# H21R4_Backend.net
KiCad netlist of a schematic drawn in Altium Designer
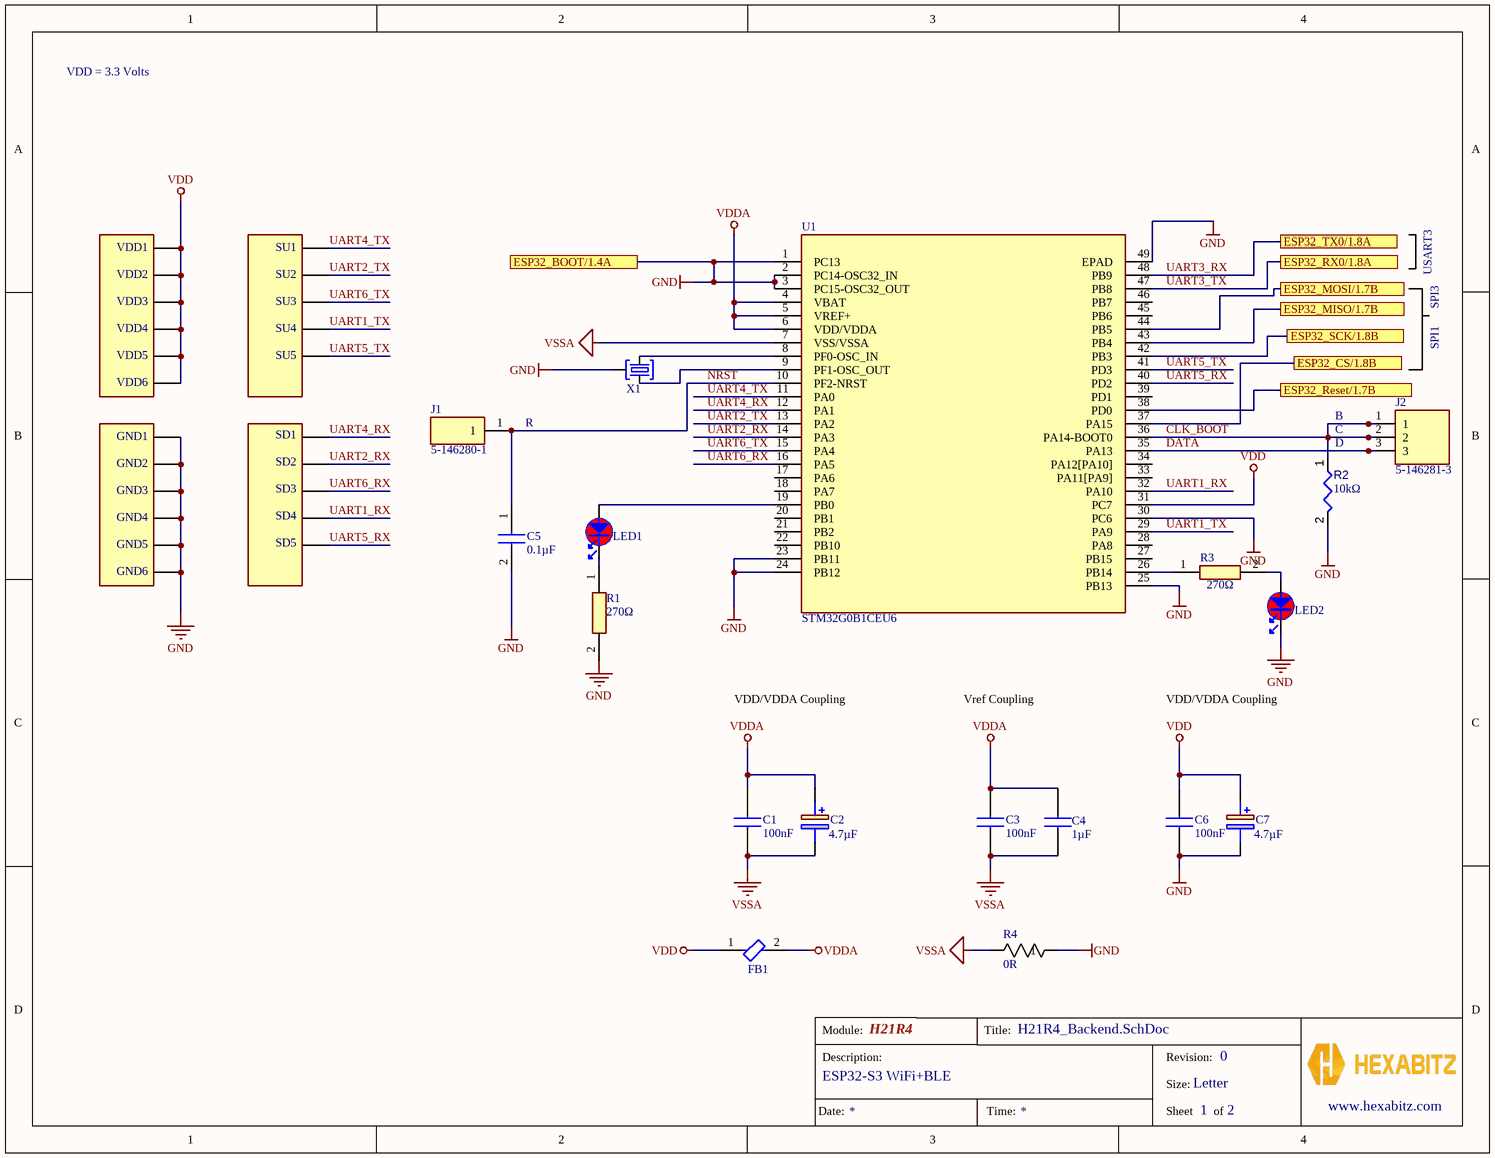
[diagram p0: H21R4_Backend.SchDoc]

(export (version "E")
  (design (tool "Eeschema 10.0.6"))
  (components
    (comp (ref "C1")
      (value "100nF")
      (footprint "CAPC1608X87N")
      (description "Multilayer Ceramic Capacitors MLCC - SMD/SMT .1UF     10V   10%        0603")
      (fields (field (name "MANUFACTURER_PART_NUMBER") "C0603C104K8RAC7867"))
      (libsource (lib "Wesley Walker") (part "C0603C104K8RAC7867"))
    )
    (comp (ref "C2")
      (value "4.7µF")
      (footprint "CAPPM2012X100N")
      (fields
        (field (name "MANUFACTURER_PART_NUMBER") "10TPU4R7MSI")
        (field (name "MOUSER PART NUMBER") "667-10TPU4R7MSI")
      )
      (libsource (lib "Wesley Walker") (part "10TPU4R7MSI"))
    )
    (comp (ref "C3")
      (value "100nF")
      (footprint "CAPC1608X87N")
      (description "Multilayer Ceramic Capacitors MLCC - SMD/SMT .1UF     10V   10%        0603")
      (fields (field (name "MANUFACTURER_PART_NUMBER") "C0603C104K8RAC7867"))
      (libsource (lib "Wesley Walker") (part "C0603C104K8RAC7867"))
    )
    (comp (ref "C4")
      (value "1µF")
      (footprint "CAPC2012X145N")
      (fields
        (field (name "ARROW PART NUMBER") "CC0805KKX7R7BB105")
        (field (name "MOUSER PART NUMBER") "603-CC805KKX7R7BB105")
      )
      (libsource (lib "Wesley Walker") (part "CC0805KKX7R7BB105"))
    )
    (comp (ref "C5")
      (value "0.1µF")
      (footprint "SamacSys:CAPC1608X87N")
      (description "Capacitor")
      (fields (field (name "MANUFACTURER_PART_NUMBER") "C0603C104K8RAC7867"))
      (libsource (lib "*") (part "C0603C104K8RAC7867"))
    )
    (comp (ref "C6")
      (value "100nF")
      (footprint "CAPC1608X87N")
      (description "Multilayer Ceramic Capacitors MLCC - SMD/SMT .1UF     10V   10%        0603")
      (fields (field (name "MANUFACTURER_PART_NUMBER") "C0603C104K8RAC7867"))
      (libsource (lib "Wesley Walker") (part "C0603C104K8RAC7867"))
    )
    (comp (ref "C7")
      (value "4.7µF")
      (footprint "CAPPM2012X100N")
      (fields
        (field (name "MANUFACTURER_PART_NUMBER") "10TPU4R7MSI")
        (field (name "MOUSER PART NUMBER") "667-10TPU4R7MSI")
      )
      (libsource (lib "Wesley Walker") (part "10TPU4R7MSI"))
    )
    (comp (ref "FB1")
      (value "MMZ1608Y300B")
      (footprint "FP-MMZ1608-0_8-MFG")
      (description "Ferrite Beads 0603 30ohms 1500mA Signal Line AEC-Q200")
      (fields
        (field (name "MANUFACTURER PART NUMBER") "MMZ1608Y300BTD25")
        (field (name "MANUFACTURER") "TDK")
      )
      (libsource (lib "Wesley Walker") (part "MMZ1608Y300B"))
    )
    (comp (ref "GND1")
      (value "HEXABIT_UART_PORT")
      (footprint "HEXABIT_POWER_PORT_D")
      (libsource (lib "hexabitz_connectors.Library") (part "HEXABIT_POWER_PORT_D"))
    )
    (comp (ref "GND2")
      (value "HEXABIT_UART_PORT")
      (footprint "HEXABIT_POWER_PORT_D")
      (libsource (lib "hexabitz_connectors.Library") (part "HEXABIT_POWER_PORT_D"))
    )
    (comp (ref "GND3")
      (value "HEXABIT_UART_PORT")
      (footprint "HEXABIT_POWER_PORT_D")
      (libsource (lib "hexabitz_connectors.Library") (part "HEXABIT_POWER_PORT_D"))
    )
    (comp (ref "GND4")
      (value "HEXABIT_UART_PORT")
      (footprint "HEXABIT_POWER_PORT_D")
      (libsource (lib "hexabitz_connectors.Library") (part "HEXABIT_POWER_PORT_D"))
    )
    (comp (ref "GND5")
      (value "HEXABIT_UART_PORT")
      (footprint "HEXABIT_POWER_PORT_D")
      (libsource (lib "hexabitz_connectors.Library") (part "HEXABIT_POWER_PORT_D"))
    )
    (comp (ref "GND6")
      (value "HEXABIT_UART_PORT")
      (footprint "HEXABIT_POWER_PORT_D")
      (libsource (lib "hexabitz_connectors.Library") (part "HEXABIT_POWER_PORT_D"))
    )
    (comp (ref "J1")
      (value "5-146280-1")
      (footprint "HDRV1W67P0X254_1X1_213X234X821P")
      (description "AMP - TE CONNECTIVITY - 5-146280-1 - 01 MODII HDR SRST B/A LF")
      (fields (field (name "MOUSER PART NUMBER") "571-51462801"))
      (libsource (lib "Wesley Walker") (part "5-146280-1"))
    )
    (comp (ref "J2")
      (value "5-146281-3")
      (footprint "SamacSys:HDRV3W96P0X254_1X3_721X234X869P")
      (description "Connector")
      (fields (field (name "MOUSER PART NUMBER") "571-5-146281-3"))
      (libsource (lib "*") (part "5-146281-3"))
    )
    (comp (ref "LED1")
      (value "VLMS1300-GS08")
      (footprint "FP-6_541-5092_01-4-MFG")
      (description "LED Uni-Color Super Red 639nm 2-Pin Chip 0603(1608Metric) T/R")
      (fields (field (name "MANUFACTURER") "Vishay Semiconductors"))
      (libsource (lib "Wesley Walker") (part "VLMS1300-GS08"))
    )
    (comp (ref "LED2")
      (value "VLMS1300-GS08")
      (footprint "FP-6_541-5092_01-4-MFG")
      (description "LED Uni-Color Super Red 639nm 2-Pin Chip 0603(1608Metric) T/R")
      (fields (field (name "MANUFACTURER") "Vishay Semiconductors"))
      (libsource (lib "Wesley Walker") (part "VLMS1300-GS08"))
    )
    (comp (ref "R1")
      (value "270Ω")
      (footprint "SamacSys:ERJ3EKF1000V")
      (description "Resistor")
      (fields
        (field (name "MANUFACTURER_PART_NUMBER") "ERJ-3GEYJ271V")
        (field (name "MOUSER PART NUMBER") "667-ERJ-3GEYJ271V")
      )
      (libsource (lib "*") (part "ERJ-3GEYJ271V"))
    )
    (comp (ref "R2")
      (value "10kΩ")
      (footprint "RESC1608X55X25ML10T15")
      (description "Chip Resistor, 10 KOhm, +/- 1%, 01 W, -55 to 155 degC, 0603 (1608 Metric)")
      (fields (field (name "POWER") "100mW") (field (name "TOLERANCE") "1%"))
      (libsource (lib "Wesley Walker") (part "RES-2"))
    )
    (comp (ref "R3")
      (value "270Ω")
      (footprint "SamacSys:ERJ3EKF1000V")
      (description "Resistor")
      (fields
        (field (name "MANUFACTURER_PART_NUMBER") "ERJ-3GEYJ271V")
        (field (name "MOUSER PART NUMBER") "667-ERJ-3GEYJ271V")
      )
      (libsource (lib "") (part "ERJ-3GEYJ271V_1"))
    )
    (comp (ref "R4")
      (value "0R")
      (footprint "YAG_AC0402_YAG")
      (description "No Description Available")
      (fields
        (field (name "MANUFACTURER_PART_NUMBER") "AC0402JR-070RL")
        (field (name "COPYRIGHT") "Copyright (C) 2025 Ultra Librarian. All rights reserved.")
      )
      (libsource (lib "Wesley Walker") (part "AC0402JR-070RL"))
    )
    (comp (ref "SD1")
      (value "HEXABIT_UART_PORT")
      (footprint "HEXABIT_UART_PORT_D")
      (libsource (lib "hexabitz_connectors.Library") (part "HEXABIT_UART_PORT_D"))
    )
    (comp (ref "SD2")
      (value "HEXABIT_UART_PORT")
      (footprint "HEXABIT_UART_PORT_D")
      (libsource (lib "hexabitz_connectors.Library") (part "HEXABIT_UART_PORT_D"))
    )
    (comp (ref "SD3")
      (value "HEXABIT_UART_PORT")
      (footprint "HEXABIT_UART_PORT_D")
      (libsource (lib "hexabitz_connectors.Library") (part "HEXABIT_UART_PORT_D"))
    )
    (comp (ref "SD4")
      (value "HEXABIT_UART_PORT")
      (footprint "HEXABIT_UART_PORT_D")
      (libsource (lib "hexabitz_connectors.Library") (part "HEXABIT_UART_PORT_D"))
    )
    (comp (ref "SD5")
      (value "HEXABIT_UART_PORT")
      (footprint "HEXABIT_UART_PORT_D")
      (libsource (lib "hexabitz_connectors.Library") (part "HEXABIT_UART_PORT_D"))
    )
    (comp (ref "SU1")
      (value "HEXABIT_UART_PORT")
      (footprint "HEXABIT_UART_PORT_U")
      (libsource (lib "hexabitz_connectors.Library") (part "HEXABIT_UART_PORT_U"))
    )
    (comp (ref "SU2")
      (value "HEXABIT_UART_PORT")
      (footprint "HEXABIT_UART_PORT_U")
      (libsource (lib "hexabitz_connectors.Library") (part "HEXABIT_UART_PORT_U"))
    )
    (comp (ref "SU3")
      (value "HEXABIT_UART_PORT")
      (footprint "HEXABIT_UART_PORT_U")
      (libsource (lib "hexabitz_connectors.Library") (part "HEXABIT_UART_PORT_U"))
    )
    (comp (ref "SU4")
      (value "HEXABIT_UART_PORT")
      (footprint "HEXABIT_UART_PORT_U")
      (libsource (lib "hexabitz_connectors.Library") (part "HEXABIT_UART_PORT_U"))
    )
    (comp (ref "SU5")
      (value "HEXABIT_UART_PORT")
      (footprint "HEXABIT_UART_PORT_U")
      (libsource (lib "hexabitz_connectors.Library") (part "HEXABIT_UART_PORT_U"))
    )
    (comp (ref "U1")
      (value "STM32G0B1CEU6")
      (footprint "QFN50P700X700X65-49N-D")
      (description "MCU 32-bit ARM Cortex M0+ RISC 512KB Flash 1.8V/2.5V/3.3V 48-Pin UFQFPN EP Tray")
      (fields (field (name "MANUFACTURER") "STMicroelectronics"))
      (libsource (lib "Wesley Walker") (part "STM32G0B1CEU6"))
    )
    (comp (ref "VDD1")
      (value "HEXABIT_UART_PORT")
      (footprint "HEXABIT_POWER_PORT_U")
      (libsource (lib "hexabitz_connectors.Library") (part "HEXABIT_POWER_PORT_U"))
    )
    (comp (ref "VDD2")
      (value "HEXABIT_UART_PORT")
      (footprint "HEXABIT_POWER_PORT_U")
      (libsource (lib "hexabitz_connectors.Library") (part "HEXABIT_POWER_PORT_U"))
    )
    (comp (ref "VDD3")
      (value "HEXABIT_UART_PORT")
      (footprint "HEXABIT_POWER_PORT_U")
      (libsource (lib "hexabitz_connectors.Library") (part "HEXABIT_POWER_PORT_U"))
    )
    (comp (ref "VDD4")
      (value "HEXABIT_UART_PORT")
      (footprint "HEXABIT_POWER_PORT_U")
      (libsource (lib "hexabitz_connectors.Library") (part "HEXABIT_POWER_PORT_U"))
    )
    (comp (ref "VDD5")
      (value "HEXABIT_UART_PORT")
      (footprint "HEXABIT_POWER_PORT_U")
      (libsource (lib "hexabitz_connectors.Library") (part "HEXABIT_POWER_PORT_U"))
    )
    (comp (ref "VDD6")
      (value "HEXABIT_UART_PORT")
      (footprint "HEXABIT_POWER_PORT_U")
      (libsource (lib "hexabitz_connectors.Library") (part "HEXABIT_POWER_PORT_U"))
    )
    (comp (ref "X1")
      (value "CSTCE8M00G52Z-R0")
      (footprint "XTALL_CSTCE8M00G52")
      (description "Ceramic Resonator 8MHz ±0.5% (Tol) ±0.2% (Stability) 10pF 40Ohm 3-Pin CSMD T/R")
      (fields (field (name "TOLERANCE") "0.5%") (field (name "MANUFACTURER") "Murata"))
      (libsource (lib "Wesley Walker") (part "CSTCE8M00G52Z-R0"))
    )
  )
  (nets
    (net (code "1") (name "/CLK_BOOT") (class "Default")
      (node (ref "J2") (pin "1") (pinfunction "1_1") (pintype "passive"))
      (node (ref "J2") (pin "2") (pinfunction "2_2") (pintype "passive"))
      (node (ref "R2") (pin "1") (pinfunction "1_1") (pintype "passive"))
      (node (ref "U1") (pin "36") (pinfunction "PA14-BOOT0_36") (pintype "passive"))
    )
    (net (code "2") (name "/DATA") (class "Default")
      (node (ref "J2") (pin "3") (pinfunction "3_3") (pintype "passive"))
      (node (ref "U1") (pin "35") (pinfunction "PA13_35") (pintype "passive"))
    )
    (net (code "3") (name "/ESP32_CS{slash}1.8B") (class "Default")
      (node (ref "U1") (pin "37") (pinfunction "PA15_37") (pintype "passive"))
    )
    (net (code "4") (name "/ESP32_MISO{slash}1.7B") (class "Default")
      (node (ref "U1") (pin "43") (pinfunction "PB4_43") (pintype "passive"))
    )
    (net (code "5") (name "/ESP32_MOSI{slash}1.7B") (class "Default")
      (node (ref "U1") (pin "44") (pinfunction "PB5_44") (pintype "passive"))
    )
    (net (code "6") (name "/ESP32_Reset{slash}1.7B") (class "Default")
      (node (ref "U1") (pin "38") (pinfunction "PD0_38") (pintype "passive"))
    )
    (net (code "7") (name "/ESP32_SCK{slash}1.8B") (class "Default")
      (node (ref "U1") (pin "42") (pinfunction "PB3_42") (pintype "passive"))
    )
    (net (code "8") (name "/NRST") (class "Default")
      (node (ref "C5") (pin "1") (pinfunction "1_1") (pintype "passive"))
      (node (ref "J1") (pin "1") (pinfunction "1_1") (pintype "passive"))
      (node (ref "U1") (pin "10") (pinfunction "PF2-NRST_10") (pintype "passive"))
    )
    (net (code "9") (name "/UART1_RX") (class "Default")
      (node (ref "SD4") (pin "UART_D") (pinfunction "UART_D_UART_D") (pintype "passive"))
      (node (ref "U1") (pin "32") (pinfunction "PA10_32") (pintype "passive"))
    )
    (net (code "10") (name "/UART1_TX") (class "Default")
      (node (ref "SU4") (pin "UART_U") (pinfunction "UART_U_UART_U") (pintype "passive"))
      (node (ref "U1") (pin "29") (pinfunction "PA9_29") (pintype "passive"))
    )
    (net (code "11") (name "/UART2_RX") (class "Default")
      (node (ref "SD2") (pin "UART_D") (pinfunction "UART_D_UART_D") (pintype "passive"))
      (node (ref "U1") (pin "14") (pinfunction "PA3_14") (pintype "passive"))
    )
    (net (code "12") (name "/UART2_TX") (class "Default")
      (node (ref "SU2") (pin "UART_U") (pinfunction "UART_U_UART_U") (pintype "passive"))
      (node (ref "U1") (pin "13") (pinfunction "PA2_13") (pintype "passive"))
    )
    (net (code "13") (name "/UART3_RX") (class "Default")
      (node (ref "U1") (pin "48") (pinfunction "PB9_48") (pintype "passive"))
    )
    (net (code "14") (name "/UART3_TX") (class "Default")
      (node (ref "U1") (pin "47") (pinfunction "PB8_47") (pintype "passive"))
    )
    (net (code "15") (name "/UART4_RX") (class "Default")
      (node (ref "SD1") (pin "UART_D") (pinfunction "UART_D_UART_D") (pintype "passive"))
      (node (ref "U1") (pin "12") (pinfunction "PA1_12") (pintype "passive"))
    )
    (net (code "16") (name "/UART4_TX") (class "Default")
      (node (ref "SU1") (pin "UART_U") (pinfunction "UART_U_UART_U") (pintype "passive"))
      (node (ref "U1") (pin "11") (pinfunction "PA0_11") (pintype "passive"))
    )
    (net (code "17") (name "/UART5_RX") (class "Default")
      (node (ref "SD5") (pin "UART_D") (pinfunction "UART_D_UART_D") (pintype "passive"))
      (node (ref "U1") (pin "40") (pinfunction "PD2_40") (pintype "passive"))
    )
    (net (code "18") (name "/UART5_TX") (class "Default")
      (node (ref "SU5") (pin "UART_U") (pinfunction "UART_U_UART_U") (pintype "passive"))
      (node (ref "U1") (pin "41") (pinfunction "PD3_41") (pintype "passive"))
    )
    (net (code "19") (name "/UART6_RX") (class "Default")
      (node (ref "SD3") (pin "UART_D") (pinfunction "UART_D_UART_D") (pintype "passive"))
      (node (ref "U1") (pin "16") (pinfunction "PA5_16") (pintype "passive"))
    )
    (net (code "20") (name "/UART6_TX") (class "Default")
      (node (ref "SU3") (pin "UART_U") (pinfunction "UART_U_UART_U") (pintype "passive"))
      (node (ref "U1") (pin "15") (pinfunction "PA4_15") (pintype "passive"))
    )
    (net (code "21") (name "GND") (class "Default")
      (node (ref "C5") (pin "2") (pinfunction "2_2") (pintype "passive"))
      (node (ref "C6") (pin "1") (pinfunction "1_1") (pintype "passive"))
      (node (ref "C7") (pin "2") (pinfunction "-_2") (pintype "passive"))
      (node (ref "GND1") (pin "Pwr_D") (pinfunction "Pwr_D_Pwr_D") (pintype "passive"))
      (node (ref "GND2") (pin "Pwr_D") (pinfunction "Pwr_D_Pwr_D") (pintype "passive"))
      (node (ref "GND3") (pin "Pwr_D") (pinfunction "Pwr_D_Pwr_D") (pintype "passive"))
      (node (ref "GND4") (pin "Pwr_D") (pinfunction "Pwr_D_Pwr_D") (pintype "passive"))
      (node (ref "GND5") (pin "Pwr_D") (pinfunction "Pwr_D_Pwr_D") (pintype "passive"))
      (node (ref "GND6") (pin "Pwr_D") (pinfunction "Pwr_D_Pwr_D") (pintype "passive"))
      (node (ref "LED2") (pin "1") (pintype "passive"))
      (node (ref "R1") (pin "2") (pinfunction "2_2") (pintype "passive"))
      (node (ref "R2") (pin "2") (pinfunction "2_2") (pintype "passive"))
      (node (ref "R4") (pin "1") (pinfunction "1_1") (pintype "passive"))
      (node (ref "U1") (pin "1") (pinfunction "PC13_1") (pintype "passive"))
      (node (ref "U1") (pin "2") (pinfunction "PC14-OSC32_IN_2") (pintype "passive"))
      (node (ref "U1") (pin "23") (pinfunction "PB11_23") (pintype "passive"))
      (node (ref "U1") (pin "24") (pinfunction "PB12_24") (pintype "passive"))
      (node (ref "U1") (pin "25") (pinfunction "PB13_25") (pintype "passive"))
      (node (ref "U1") (pin "3") (pinfunction "PC15-OSC32_OUT_3") (pintype "passive"))
      (node (ref "U1") (pin "30") (pinfunction "PC6_30") (pintype "passive"))
      (node (ref "U1") (pin "49") (pinfunction "EPAD_49") (pintype "passive"))
      (node (ref "X1") (pin "P$2") (pinfunction "2_P$2") (pintype "passive"))
    )
    (net (code "22") (name "Net-(LED1-Pad1)") (class "Default")
      (node (ref "LED1") (pin "1") (pintype "passive"))
      (node (ref "R1") (pin "1") (pinfunction "1_1") (pintype "passive"))
    )
    (net (code "23") (name "Net-(LED2-Pad2)") (class "Default")
      (node (ref "LED2") (pin "2") (pintype "passive"))
      (node (ref "R3") (pin "2") (pinfunction "2_2") (pintype "passive"))
    )
    (net (code "24") (name "Net-(U1-PB0)") (class "Default")
      (node (ref "LED1") (pin "2") (pintype "passive"))
      (node (ref "U1") (pin "19") (pinfunction "PB0_19") (pintype "passive"))
    )
    (net (code "25") (name "Net-(U1-PB14)") (class "Default")
      (node (ref "R3") (pin "1") (pinfunction "1_1") (pintype "passive"))
      (node (ref "U1") (pin "26") (pinfunction "PB14_26") (pintype "passive"))
    )
    (net (code "26") (name "Net-(U1-PF0-OSC_IN)") (class "Default")
      (node (ref "U1") (pin "8") (pinfunction "PF0-OSC_IN_8") (pintype "passive"))
      (node (ref "X1") (pin "P$1") (pinfunction "1_P$1") (pintype "passive"))
    )
    (net (code "27") (name "Net-(U1-PF1-OSC_OUT)") (class "Default")
      (node (ref "U1") (pin "9") (pinfunction "PF1-OSC_OUT_9") (pintype "passive"))
      (node (ref "X1") (pin "P$3") (pinfunction "3_P$3") (pintype "passive"))
    )
    (net (code "28") (name "VDD") (class "Default")
      (node (ref "C6") (pin "2") (pinfunction "2_2") (pintype "passive"))
      (node (ref "C7") (pin "1") (pinfunction "+_1") (pintype "passive"))
      (node (ref "FB1") (pin "1") (pinfunction "1_1") (pintype "passive"))
      (node (ref "U1") (pin "31") (pinfunction "PC7_31") (pintype "passive"))
      (node (ref "VDD1") (pin "Pwr_U") (pinfunction "Pwr_U_Pwr_U") (pintype "passive"))
      (node (ref "VDD2") (pin "Pwr_U") (pinfunction "Pwr_U_Pwr_U") (pintype "passive"))
      (node (ref "VDD3") (pin "Pwr_U") (pinfunction "Pwr_U_Pwr_U") (pintype "passive"))
      (node (ref "VDD4") (pin "Pwr_U") (pinfunction "Pwr_U_Pwr_U") (pintype "passive"))
      (node (ref "VDD5") (pin "Pwr_U") (pinfunction "Pwr_U_Pwr_U") (pintype "passive"))
      (node (ref "VDD6") (pin "Pwr_U") (pinfunction "Pwr_U_Pwr_U") (pintype "passive"))
    )
    (net (code "29") (name "VDDA") (class "Default")
      (node (ref "C1") (pin "2") (pinfunction "2_2") (pintype "passive"))
      (node (ref "C2") (pin "1") (pinfunction "+_1") (pintype "passive"))
      (node (ref "C3") (pin "2") (pinfunction "2_2") (pintype "passive"))
      (node (ref "C4") (pin "1") (pinfunction "1_1") (pintype "passive"))
      (node (ref "FB1") (pin "2") (pinfunction "2_2") (pintype "passive"))
      (node (ref "U1") (pin "4") (pinfunction "VBAT_4") (pintype "passive"))
      (node (ref "U1") (pin "5") (pinfunction "VREF+_5") (pintype "passive"))
      (node (ref "U1") (pin "6") (pinfunction "VDD/VDDA_6") (pintype "passive"))
    )
    (net (code "30") (name "VSSA") (class "Default")
      (node (ref "C1") (pin "1") (pinfunction "1_1") (pintype "passive"))
      (node (ref "C2") (pin "2") (pinfunction "-_2") (pintype "passive"))
      (node (ref "C3") (pin "1") (pinfunction "1_1") (pintype "passive"))
      (node (ref "C4") (pin "2") (pinfunction "2_2") (pintype "passive"))
      (node (ref "R4") (pin "2") (pinfunction "2_2") (pintype "passive"))
      (node (ref "U1") (pin "7") (pinfunction "VSS/VSSA_7") (pintype "passive"))
    )
    (net (code "31") (name "unconnected-(U1-PA6-Pad17)") (class "Default")
      (node (ref "U1") (pin "17") (pinfunction "PA6_17") (pintype "passive"))
    )
    (net (code "32") (name "unconnected-(U1-PA7-Pad18)") (class "Default")
      (node (ref "U1") (pin "18") (pinfunction "PA7_18") (pintype "passive"))
    )
    (net (code "33") (name "unconnected-(U1-PA8-Pad28)") (class "Default")
      (node (ref "U1") (pin "28") (pinfunction "PA8_28") (pintype "passive"))
    )
    (net (code "34") (name "unconnected-(U1-PA11[PA9]-Pad33)") (class "Default")
      (node (ref "U1") (pin "33") (pinfunction "PA11[PA9]_33") (pintype "passive"))
    )
    (net (code "35") (name "unconnected-(U1-PA12[PA10]-Pad34)") (class "Default")
      (node (ref "U1") (pin "34") (pinfunction "PA12[PA10]_34") (pintype "passive"))
    )
    (net (code "36") (name "unconnected-(U1-PB1-Pad20)") (class "Default")
      (node (ref "U1") (pin "20") (pinfunction "PB1_20") (pintype "passive"))
    )
    (net (code "37") (name "unconnected-(U1-PB2-Pad21)") (class "Default")
      (node (ref "U1") (pin "21") (pinfunction "PB2_21") (pintype "passive"))
    )
    (net (code "38") (name "unconnected-(U1-PB6-Pad45)") (class "Default")
      (node (ref "U1") (pin "45") (pinfunction "PB6_45") (pintype "passive"))
    )
    (net (code "39") (name "unconnected-(U1-PB7-Pad46)") (class "Default")
      (node (ref "U1") (pin "46") (pinfunction "PB7_46") (pintype "passive"))
    )
    (net (code "40") (name "unconnected-(U1-PB10-Pad22)") (class "Default")
      (node (ref "U1") (pin "22") (pinfunction "PB10_22") (pintype "passive"))
    )
    (net (code "41") (name "unconnected-(U1-PB15-Pad27)") (class "Default")
      (node (ref "U1") (pin "27") (pinfunction "PB15_27") (pintype "passive"))
    )
    (net (code "42") (name "unconnected-(U1-PD1-Pad39)") (class "Default")
      (node (ref "U1") (pin "39") (pinfunction "PD1_39") (pintype "passive"))
    )
  )
)
